# system_rfid_online.net
KiCad netlist of a schematic drawn in EasyEDA
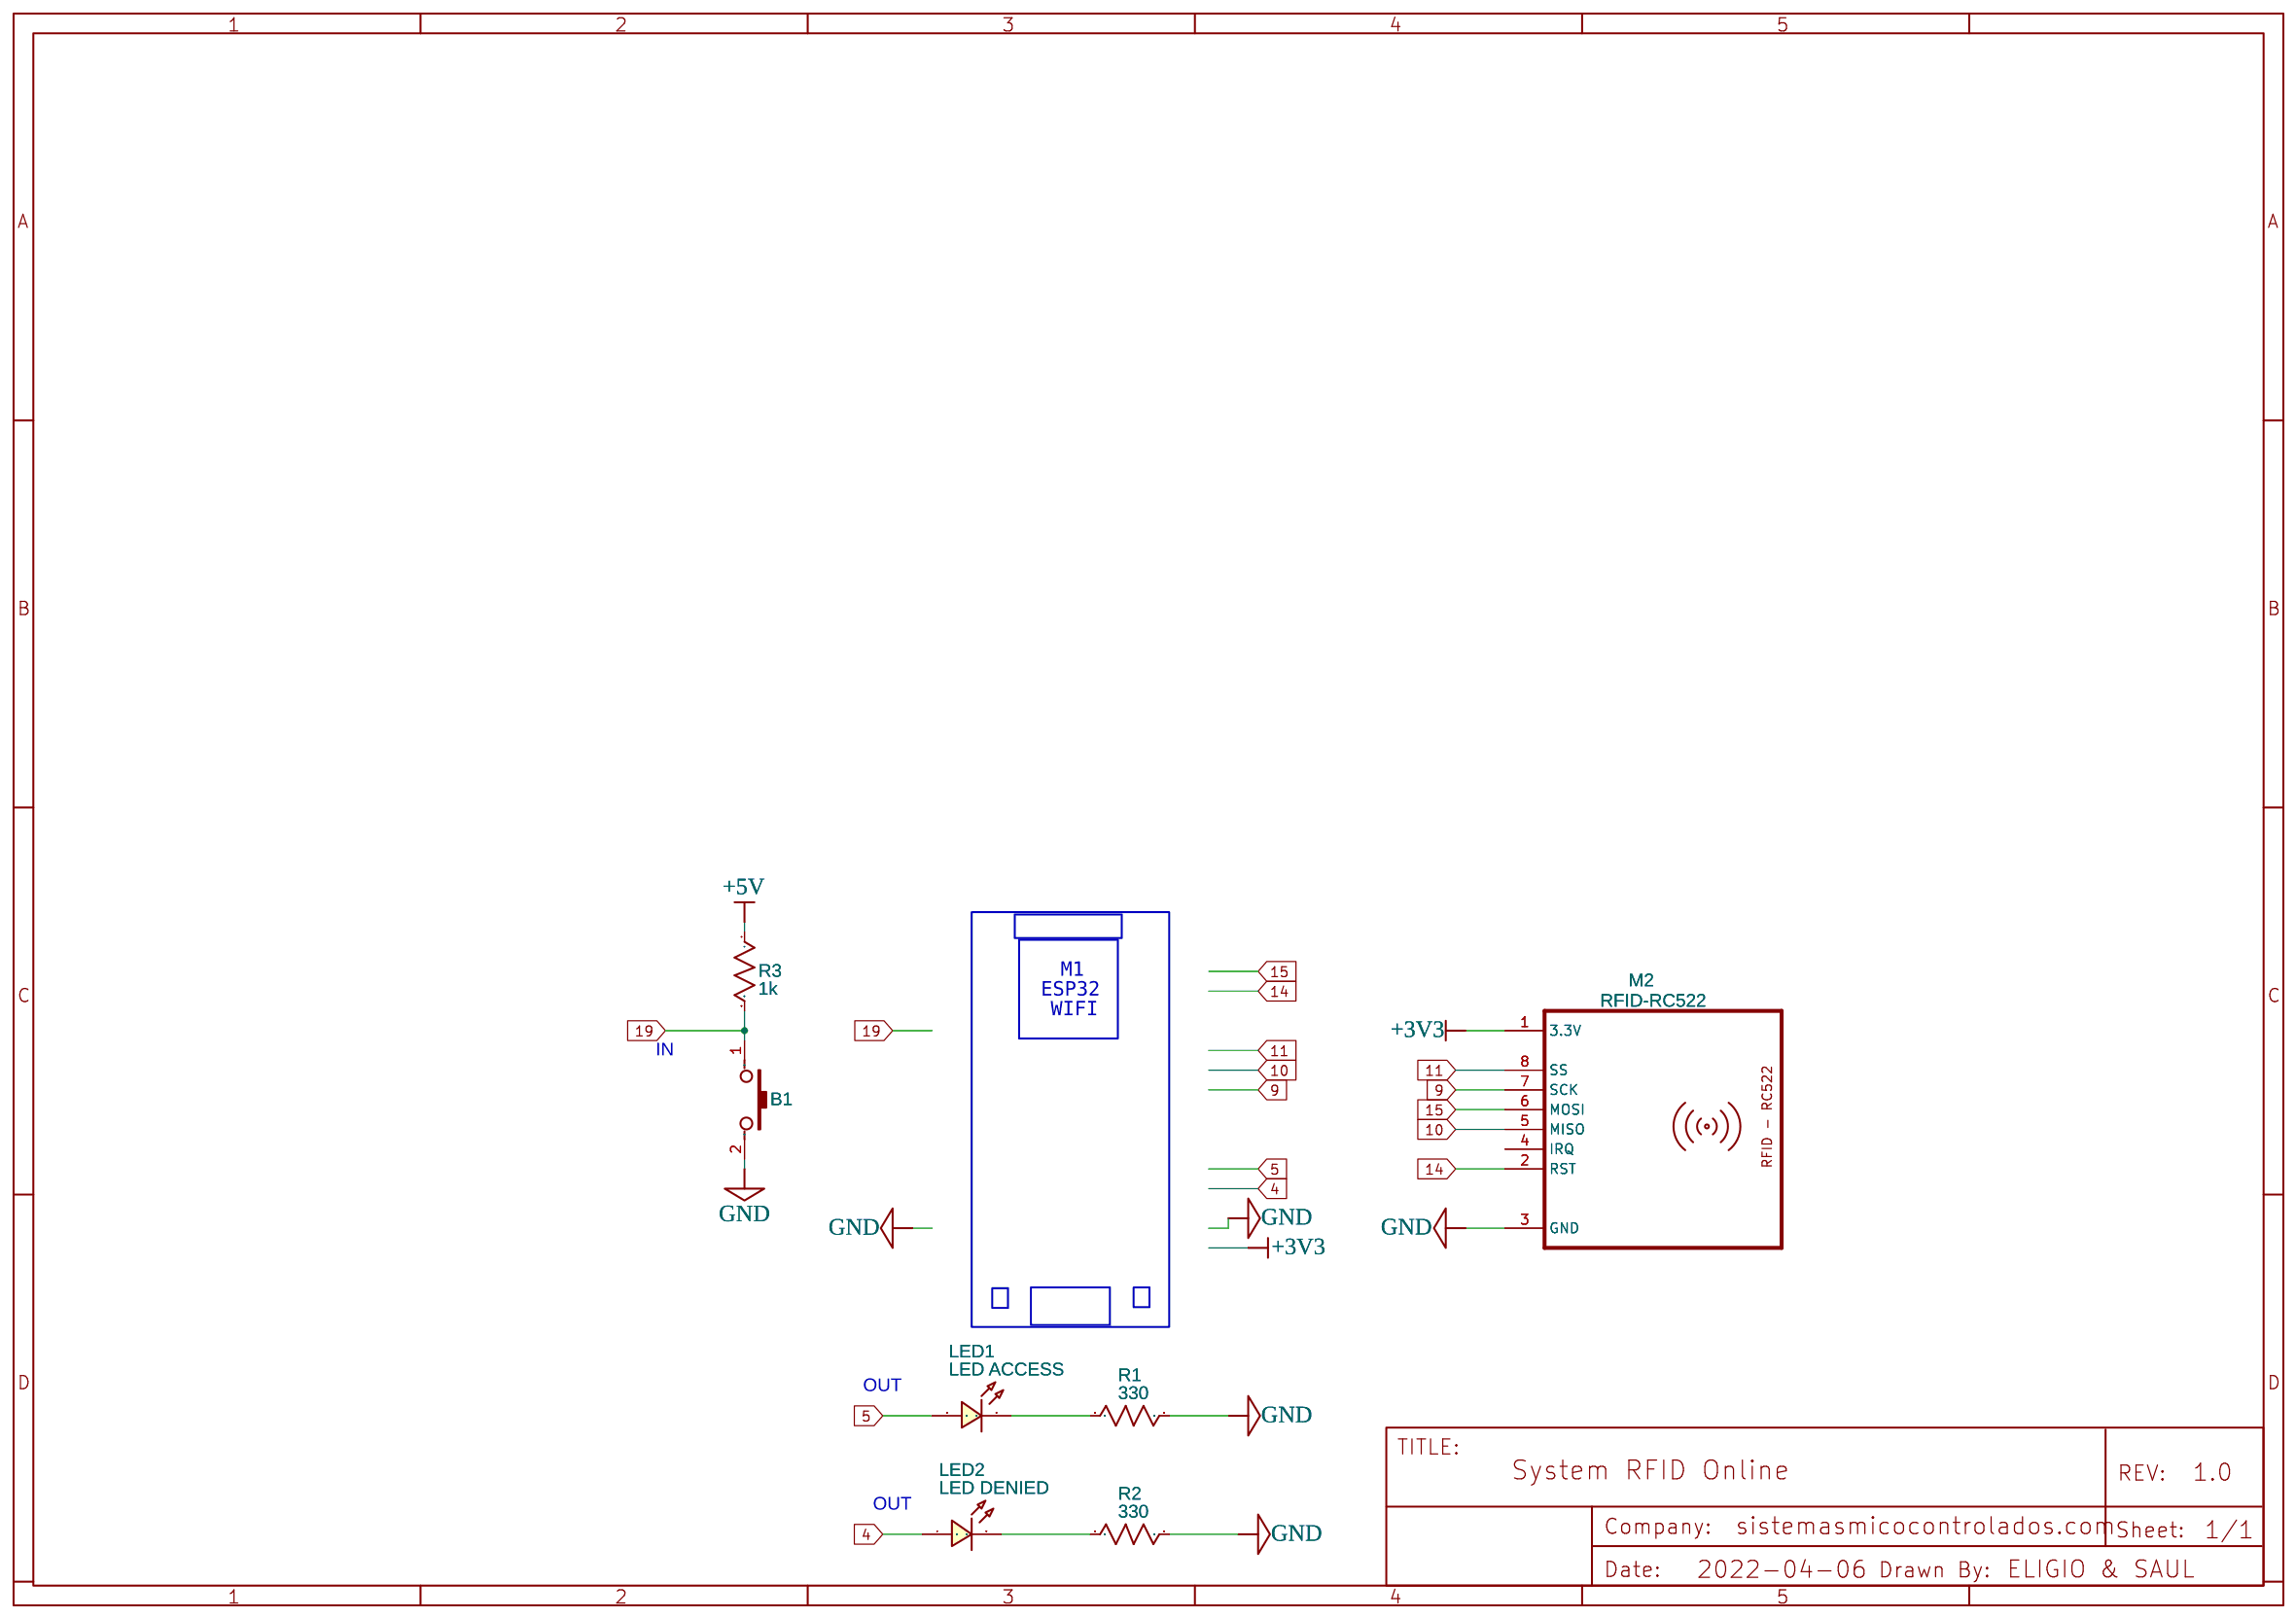
[diagram p0: schematic sheet]

(export (version "E")
  (design (tool "Eeschema 10.0.6"))
  (components
    (comp (ref "B1")
      (value "BotonProto1x2")
      (fields
        (field (name "BOM_Manufacturer Part") "ESP-12F(ESP8266MOD)")
        (field (name "BOM_Supplier Part") "BTMWESP")
      )
      (libsource (lib "") (part "BotonProto1x2"))
    )
    (comp (ref "LED1")
      (value "LED ACCESS")
      (fields
        (field (name "BOM_Manufacturer Part") "333-2SYGD/S530-E2")
        (field (name "BOM_Supplier Part") "C88163")
      )
      (libsource (lib "") (part "LED-TH-5mm_G"))
    )
    (comp (ref "LED2")
      (value "LED DENIED")
      (fields
        (field (name "BOM_Manufacturer Part") "333-2SURD/S530-A3")
        (field (name "BOM_Supplier Part") "C87271")
      )
      (libsource (lib "") (part "LED-TH-5mm_R"))
    )
    (comp (ref "M2") (value "RFID-RC522") (libsource (lib "") (part "RFID-RC522_without hols")))
    (comp (ref "R1") (value "330") (libsource (lib "") (part "R_AXIAL-1.0_US")))
    (comp (ref "R2") (value "330") (libsource (lib "") (part "R_AXIAL-1.0_US")))
    (comp (ref "R3") (value "1k") (libsource (lib "") (part "R_AXIAL-1.0_US_1")))
  )
  (nets
    (net (code "1") (name "+3V3") (class "Default")
      (node (ref "M2") (pin "1") (pinfunction "3.3V_1") (pintype "unspecified"))
    )
    (net (code "2") (name "+5V") (class "Default")
      (node (ref "R3") (pin "1") (pinfunction "1_1") (pintype "unspecified"))
    )
    (net (code "3") (name "4") (class "Default")
      (node (ref "LED2") (pin "1") (pinfunction "1_1") (pintype "unspecified"))
    )
    (net (code "4") (name "5") (class "Default")
      (node (ref "LED1") (pin "1") (pinfunction "1_1") (pintype "unspecified"))
    )
    (net (code "5") (name "9") (class "Default")
      (node (ref "M2") (pin "7") (pinfunction "SCK_7") (pintype "unspecified"))
    )
    (net (code "6") (name "10") (class "Default")
      (node (ref "M2") (pin "5") (pinfunction "MISO_5") (pintype "unspecified"))
    )
    (net (code "7") (name "11") (class "Default")
      (node (ref "M2") (pin "8") (pinfunction "SS_8") (pintype "unspecified"))
    )
    (net (code "8") (name "14") (class "Default")
      (node (ref "M2") (pin "2") (pinfunction "RST_2") (pintype "unspecified"))
    )
    (net (code "9") (name "15") (class "Default")
      (node (ref "M2") (pin "6") (pinfunction "MOSI_6") (pintype "unspecified"))
    )
    (net (code "10") (name "19") (class "Default")
      (node (ref "B1") (pin "1") (pinfunction "1_1") (pintype "input"))
      (node (ref "R3") (pin "2") (pinfunction "2_2") (pintype "unspecified"))
    )
    (net (code "11") (name "GND") (class "Default")
      (node (ref "B1") (pin "2") (pinfunction "2_2") (pintype "input"))
      (node (ref "M2") (pin "3") (pinfunction "GND_3") (pintype "unspecified"))
      (node (ref "R1") (pin "2") (pinfunction "2_2") (pintype "unspecified"))
      (node (ref "R2") (pin "2") (pinfunction "2_2") (pintype "unspecified"))
    )
    (net (code "12") (name "Net-(LED1-Pad2)") (class "Default")
      (node (ref "LED1") (pin "2") (pinfunction "2_2") (pintype "unspecified"))
      (node (ref "R1") (pin "1") (pinfunction "1_1") (pintype "unspecified"))
    )
    (net (code "13") (name "Net-(LED2-Pad2)") (class "Default")
      (node (ref "LED2") (pin "2") (pinfunction "2_2") (pintype "unspecified"))
      (node (ref "R2") (pin "1") (pinfunction "1_1") (pintype "unspecified"))
    )
    (net (code "14") (name "unconnected-(M2-IRQ-Pad4)") (class "Default")
      (node (ref "M2") (pin "4") (pinfunction "IRQ_4") (pintype "unspecified"))
    )
  )
)
